# 3DMouseMainBoardAssembly.net
KiCad netlist of a schematic drawn in Altium Designer
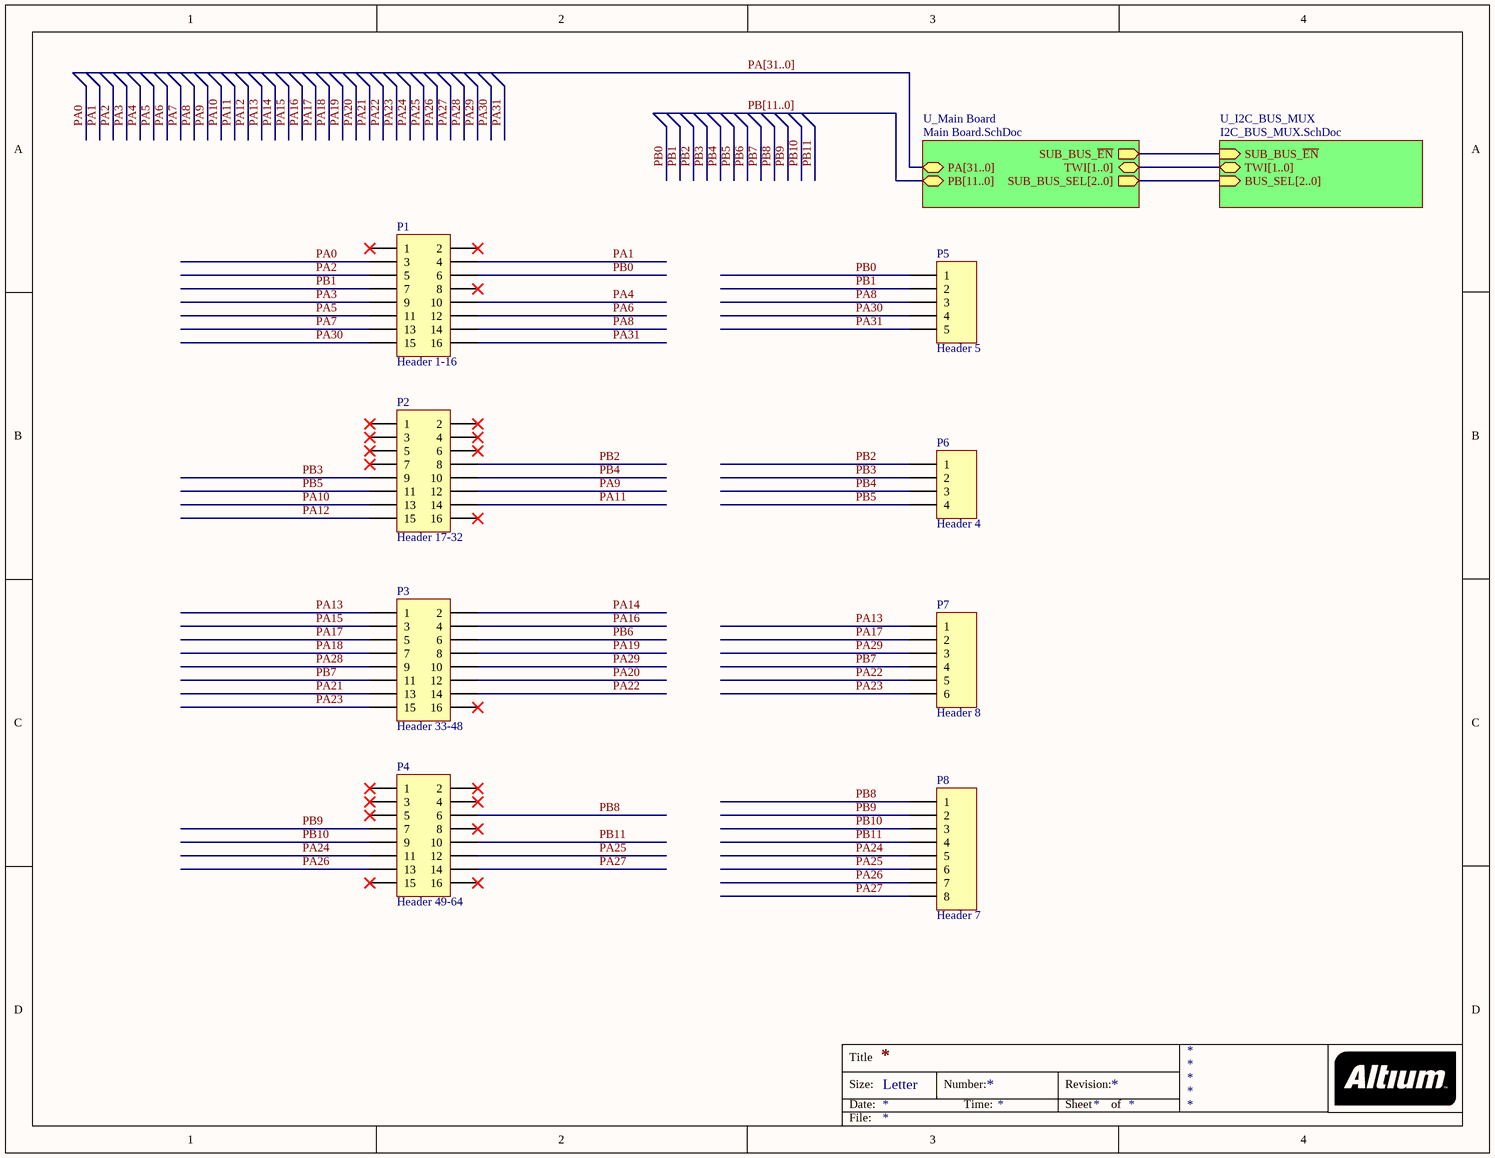
[diagram p0: 3DMouseMainBoardAssembly.SchDoc]

(export (version "E")
  (design (tool "Eeschema 10.0.6"))
  (components
    (comp (ref "P1")
      (value "Header 1-16")
      (footprint "HDR2X8")
      (description "Header, 8-Pin, Dual row")
      (fields (field (name "PUBLISHER") "Altium Limited"))
      (libsource (lib "Miscellaneous Connectors") (part "Header 8X2"))
    )
    (comp (ref "P2")
      (value "Header 17-32")
      (footprint "HDR2X8")
      (description "Header, 8-Pin, Dual row")
      (fields (field (name "PUBLISHER") "Altium Limited"))
      (libsource (lib "Miscellaneous Connectors") (part "Header 8X2"))
    )
    (comp (ref "P3")
      (value "Header 33-48")
      (footprint "HDR2X8")
      (description "Header, 8-Pin, Dual row")
      (fields (field (name "PUBLISHER") "Altium Limited"))
      (libsource (lib "Miscellaneous Connectors") (part "Header 8X2"))
    )
    (comp (ref "P4")
      (value "Header 49-64")
      (footprint "HDR2X8")
      (description "Header, 8-Pin, Dual row")
      (fields (field (name "PUBLISHER") "Altium Limited"))
      (libsource (lib "Miscellaneous Connectors") (part "Header 8X2"))
    )
    (comp (ref "P5")
      (value "Header 5")
      (footprint "HDR1X5")
      (description "Header, 5-Pin")
      (fields (field (name "PUBLISHER") "Altium Limited"))
      (libsource (lib "Miscellaneous Connectors") (part "Header 5"))
    )
    (comp (ref "P6")
      (value "Header 4")
      (footprint "HDR1X4")
      (description "Header, 4-Pin")
      (fields (field (name "PUBLISHER") "Altium Limited"))
      (libsource (lib "Miscellaneous Connectors") (part "Header 4"))
    )
    (comp (ref "P7")
      (value "Header 8")
      (footprint "HDR1X6")
      (description "Header, 6-Pin")
      (fields (field (name "PUBLISHER") "Altium Limited"))
      (libsource (lib "Miscellaneous Connectors") (part "Header 6"))
    )
    (comp (ref "P8")
      (value "Header 7")
      (footprint "HDR1X8")
      (description "Header, 8-Pin")
      (fields (field (name "PUBLISHER") "Altium Limited"))
      (libsource (lib "Miscellaneous Connectors") (part "Header 8"))
    )
  )
  (nets
    (net (code "1") (name "/PA0") (class "Default")
      (node (ref "P1") (pin "3") (pinfunction "3_3") (pintype "passive"))
    )
    (net (code "2") (name "/PA1") (class "Default")
      (node (ref "P1") (pin "4") (pinfunction "4_4") (pintype "passive"))
    )
    (net (code "3") (name "/PA2") (class "Default")
      (node (ref "P1") (pin "5") (pinfunction "5_5") (pintype "passive"))
    )
    (net (code "4") (name "/PA3") (class "Default")
      (node (ref "P1") (pin "9") (pinfunction "9_9") (pintype "passive"))
    )
    (net (code "5") (name "/PA4") (class "Default")
      (node (ref "P1") (pin "10") (pinfunction "10_10") (pintype "passive"))
    )
    (net (code "6") (name "/PA5") (class "Default")
      (node (ref "P1") (pin "11") (pinfunction "11_11") (pintype "passive"))
    )
    (net (code "7") (name "/PA6") (class "Default")
      (node (ref "P1") (pin "12") (pinfunction "12_12") (pintype "passive"))
    )
    (net (code "8") (name "/PA7") (class "Default")
      (node (ref "P1") (pin "13") (pinfunction "13_13") (pintype "passive"))
    )
    (net (code "9") (name "/PA8") (class "Default")
      (node (ref "P1") (pin "14") (pinfunction "14_14") (pintype "passive"))
      (node (ref "P5") (pin "3") (pinfunction "3_3") (pintype "passive"))
    )
    (net (code "10") (name "/PA9") (class "Default")
      (node (ref "P2") (pin "12") (pinfunction "12_12") (pintype "passive"))
    )
    (net (code "11") (name "/PA10") (class "Default")
      (node (ref "P2") (pin "13") (pinfunction "13_13") (pintype "passive"))
    )
    (net (code "12") (name "/PA11") (class "Default")
      (node (ref "P2") (pin "14") (pinfunction "14_14") (pintype "passive"))
    )
    (net (code "13") (name "/PA12") (class "Default")
      (node (ref "P2") (pin "15") (pinfunction "15_15") (pintype "passive"))
    )
    (net (code "14") (name "/PA13") (class "Default")
      (node (ref "P3") (pin "1") (pinfunction "1_1") (pintype "passive"))
      (node (ref "P7") (pin "1") (pinfunction "1_1") (pintype "passive"))
    )
    (net (code "15") (name "/PA14") (class "Default")
      (node (ref "P3") (pin "2") (pinfunction "2_2") (pintype "passive"))
    )
    (net (code "16") (name "/PA15") (class "Default")
      (node (ref "P3") (pin "3") (pinfunction "3_3") (pintype "passive"))
    )
    (net (code "17") (name "/PA16") (class "Default")
      (node (ref "P3") (pin "4") (pinfunction "4_4") (pintype "passive"))
    )
    (net (code "18") (name "/PA17") (class "Default")
      (node (ref "P3") (pin "5") (pinfunction "5_5") (pintype "passive"))
      (node (ref "P7") (pin "2") (pinfunction "2_2") (pintype "passive"))
    )
    (net (code "19") (name "/PA18") (class "Default")
      (node (ref "P3") (pin "7") (pinfunction "7_7") (pintype "passive"))
    )
    (net (code "20") (name "/PA19") (class "Default")
      (node (ref "P3") (pin "8") (pinfunction "8_8") (pintype "passive"))
    )
    (net (code "21") (name "/PA20") (class "Default")
      (node (ref "P3") (pin "12") (pinfunction "12_12") (pintype "passive"))
    )
    (net (code "22") (name "/PA21") (class "Default")
      (node (ref "P3") (pin "13") (pinfunction "13_13") (pintype "passive"))
    )
    (net (code "23") (name "/PA22") (class "Default")
      (node (ref "P3") (pin "14") (pinfunction "14_14") (pintype "passive"))
      (node (ref "P7") (pin "5") (pinfunction "5_5") (pintype "passive"))
    )
    (net (code "24") (name "/PA23") (class "Default")
      (node (ref "P3") (pin "15") (pinfunction "15_15") (pintype "passive"))
      (node (ref "P7") (pin "6") (pinfunction "6_6") (pintype "passive"))
    )
    (net (code "25") (name "/PA24") (class "Default")
      (node (ref "P4") (pin "11") (pinfunction "11_11") (pintype "passive"))
      (node (ref "P8") (pin "5") (pinfunction "5_5") (pintype "passive"))
    )
    (net (code "26") (name "/PA25") (class "Default")
      (node (ref "P4") (pin "12") (pinfunction "12_12") (pintype "passive"))
      (node (ref "P8") (pin "6") (pinfunction "6_6") (pintype "passive"))
    )
    (net (code "27") (name "/PA26") (class "Default")
      (node (ref "P4") (pin "13") (pinfunction "13_13") (pintype "passive"))
      (node (ref "P8") (pin "7") (pinfunction "7_7") (pintype "passive"))
    )
    (net (code "28") (name "/PA27") (class "Default")
      (node (ref "P4") (pin "14") (pinfunction "14_14") (pintype "passive"))
      (node (ref "P8") (pin "8") (pinfunction "8_8") (pintype "passive"))
    )
    (net (code "29") (name "/PA28") (class "Default")
      (node (ref "P3") (pin "9") (pinfunction "9_9") (pintype "passive"))
    )
    (net (code "30") (name "/PA29") (class "Default")
      (node (ref "P3") (pin "10") (pinfunction "10_10") (pintype "passive"))
      (node (ref "P7") (pin "3") (pinfunction "3_3") (pintype "passive"))
    )
    (net (code "31") (name "/PA30") (class "Default")
      (node (ref "P1") (pin "15") (pinfunction "15_15") (pintype "passive"))
      (node (ref "P5") (pin "4") (pinfunction "4_4") (pintype "passive"))
    )
    (net (code "32") (name "/PA31") (class "Default")
      (node (ref "P1") (pin "16") (pinfunction "16_16") (pintype "passive"))
      (node (ref "P5") (pin "5") (pinfunction "5_5") (pintype "passive"))
    )
    (net (code "34") (name "/PB0") (class "Default")
      (node (ref "P1") (pin "6") (pinfunction "6_6") (pintype "passive"))
      (node (ref "P5") (pin "1") (pinfunction "1_1") (pintype "passive"))
    )
    (net (code "35") (name "/PB1") (class "Default")
      (node (ref "P1") (pin "7") (pinfunction "7_7") (pintype "passive"))
      (node (ref "P5") (pin "2") (pinfunction "2_2") (pintype "passive"))
    )
    (net (code "36") (name "/PB2") (class "Default")
      (node (ref "P2") (pin "8") (pinfunction "8_8") (pintype "passive"))
      (node (ref "P6") (pin "1") (pinfunction "1_1") (pintype "passive"))
    )
    (net (code "37") (name "/PB3") (class "Default")
      (node (ref "P2") (pin "9") (pinfunction "9_9") (pintype "passive"))
      (node (ref "P6") (pin "2") (pinfunction "2_2") (pintype "passive"))
    )
    (net (code "38") (name "/PB4") (class "Default")
      (node (ref "P2") (pin "10") (pinfunction "10_10") (pintype "passive"))
      (node (ref "P6") (pin "3") (pinfunction "3_3") (pintype "passive"))
    )
    (net (code "39") (name "/PB5") (class "Default")
      (node (ref "P2") (pin "11") (pinfunction "11_11") (pintype "passive"))
      (node (ref "P6") (pin "4") (pinfunction "4_4") (pintype "passive"))
    )
    (net (code "40") (name "/PB6") (class "Default")
      (node (ref "P3") (pin "6") (pinfunction "6_6") (pintype "passive"))
    )
    (net (code "41") (name "/PB7") (class "Default")
      (node (ref "P3") (pin "11") (pinfunction "11_11") (pintype "passive"))
      (node (ref "P7") (pin "4") (pinfunction "4_4") (pintype "passive"))
    )
    (net (code "42") (name "/PB8") (class "Default")
      (node (ref "P4") (pin "6") (pinfunction "6_6") (pintype "passive"))
      (node (ref "P8") (pin "1") (pinfunction "1_1") (pintype "passive"))
    )
    (net (code "43") (name "/PB9") (class "Default")
      (node (ref "P4") (pin "7") (pinfunction "7_7") (pintype "passive"))
      (node (ref "P8") (pin "2") (pinfunction "2_2") (pintype "passive"))
    )
    (net (code "44") (name "/PB10") (class "Default")
      (node (ref "P4") (pin "9") (pinfunction "9_9") (pintype "passive"))
      (node (ref "P8") (pin "3") (pinfunction "3_3") (pintype "passive"))
    )
    (net (code "45") (name "/PB11") (class "Default")
      (node (ref "P4") (pin "10") (pinfunction "10_10") (pintype "passive"))
      (node (ref "P8") (pin "4") (pinfunction "4_4") (pintype "passive"))
    )
    (net (code "50") (name "unconnected-(P1-Pad1)") (class "Default")
      (node (ref "P1") (pin "1") (pinfunction "1_1") (pintype "passive+no_connect"))
    )
    (net (code "51") (name "unconnected-(P1-Pad2)") (class "Default")
      (node (ref "P1") (pin "2") (pinfunction "2_2") (pintype "passive+no_connect"))
    )
    (net (code "52") (name "unconnected-(P1-Pad8)") (class "Default")
      (node (ref "P1") (pin "8") (pinfunction "8_8") (pintype "passive+no_connect"))
    )
    (net (code "53") (name "unconnected-(P2-Pad1)") (class "Default")
      (node (ref "P2") (pin "1") (pinfunction "1_1") (pintype "passive+no_connect"))
    )
    (net (code "54") (name "unconnected-(P2-Pad2)") (class "Default")
      (node (ref "P2") (pin "2") (pinfunction "2_2") (pintype "passive+no_connect"))
    )
    (net (code "55") (name "unconnected-(P2-Pad3)") (class "Default")
      (node (ref "P2") (pin "3") (pinfunction "3_3") (pintype "passive+no_connect"))
    )
    (net (code "56") (name "unconnected-(P2-Pad4)") (class "Default")
      (node (ref "P2") (pin "4") (pinfunction "4_4") (pintype "passive+no_connect"))
    )
    (net (code "57") (name "unconnected-(P2-Pad5)") (class "Default")
      (node (ref "P2") (pin "5") (pinfunction "5_5") (pintype "passive+no_connect"))
    )
    (net (code "58") (name "unconnected-(P2-Pad6)") (class "Default")
      (node (ref "P2") (pin "6") (pinfunction "6_6") (pintype "passive+no_connect"))
    )
    (net (code "59") (name "unconnected-(P2-Pad7)") (class "Default")
      (node (ref "P2") (pin "7") (pinfunction "7_7") (pintype "passive+no_connect"))
    )
    (net (code "60") (name "unconnected-(P2-Pad16)") (class "Default")
      (node (ref "P2") (pin "16") (pinfunction "16_16") (pintype "passive+no_connect"))
    )
    (net (code "61") (name "unconnected-(P3-Pad16)") (class "Default")
      (node (ref "P3") (pin "16") (pinfunction "16_16") (pintype "passive+no_connect"))
    )
    (net (code "62") (name "unconnected-(P4-Pad1)") (class "Default")
      (node (ref "P4") (pin "1") (pinfunction "1_1") (pintype "passive+no_connect"))
    )
    (net (code "63") (name "unconnected-(P4-Pad2)") (class "Default")
      (node (ref "P4") (pin "2") (pinfunction "2_2") (pintype "passive+no_connect"))
    )
    (net (code "64") (name "unconnected-(P4-Pad3)") (class "Default")
      (node (ref "P4") (pin "3") (pinfunction "3_3") (pintype "passive+no_connect"))
    )
    (net (code "65") (name "unconnected-(P4-Pad4)") (class "Default")
      (node (ref "P4") (pin "4") (pinfunction "4_4") (pintype "passive+no_connect"))
    )
    (net (code "66") (name "unconnected-(P4-Pad5)") (class "Default")
      (node (ref "P4") (pin "5") (pinfunction "5_5") (pintype "passive+no_connect"))
    )
    (net (code "67") (name "unconnected-(P4-Pad8)") (class "Default")
      (node (ref "P4") (pin "8") (pinfunction "8_8") (pintype "passive+no_connect"))
    )
    (net (code "68") (name "unconnected-(P4-Pad15)") (class "Default")
      (node (ref "P4") (pin "15") (pinfunction "15_15") (pintype "passive+no_connect"))
    )
    (net (code "69") (name "unconnected-(P4-Pad16)") (class "Default")
      (node (ref "P4") (pin "16") (pinfunction "16_16") (pintype "passive+no_connect"))
    )
  )
)
